# Sheet2.net
KiCad netlist of a schematic drawn in Altium Designer
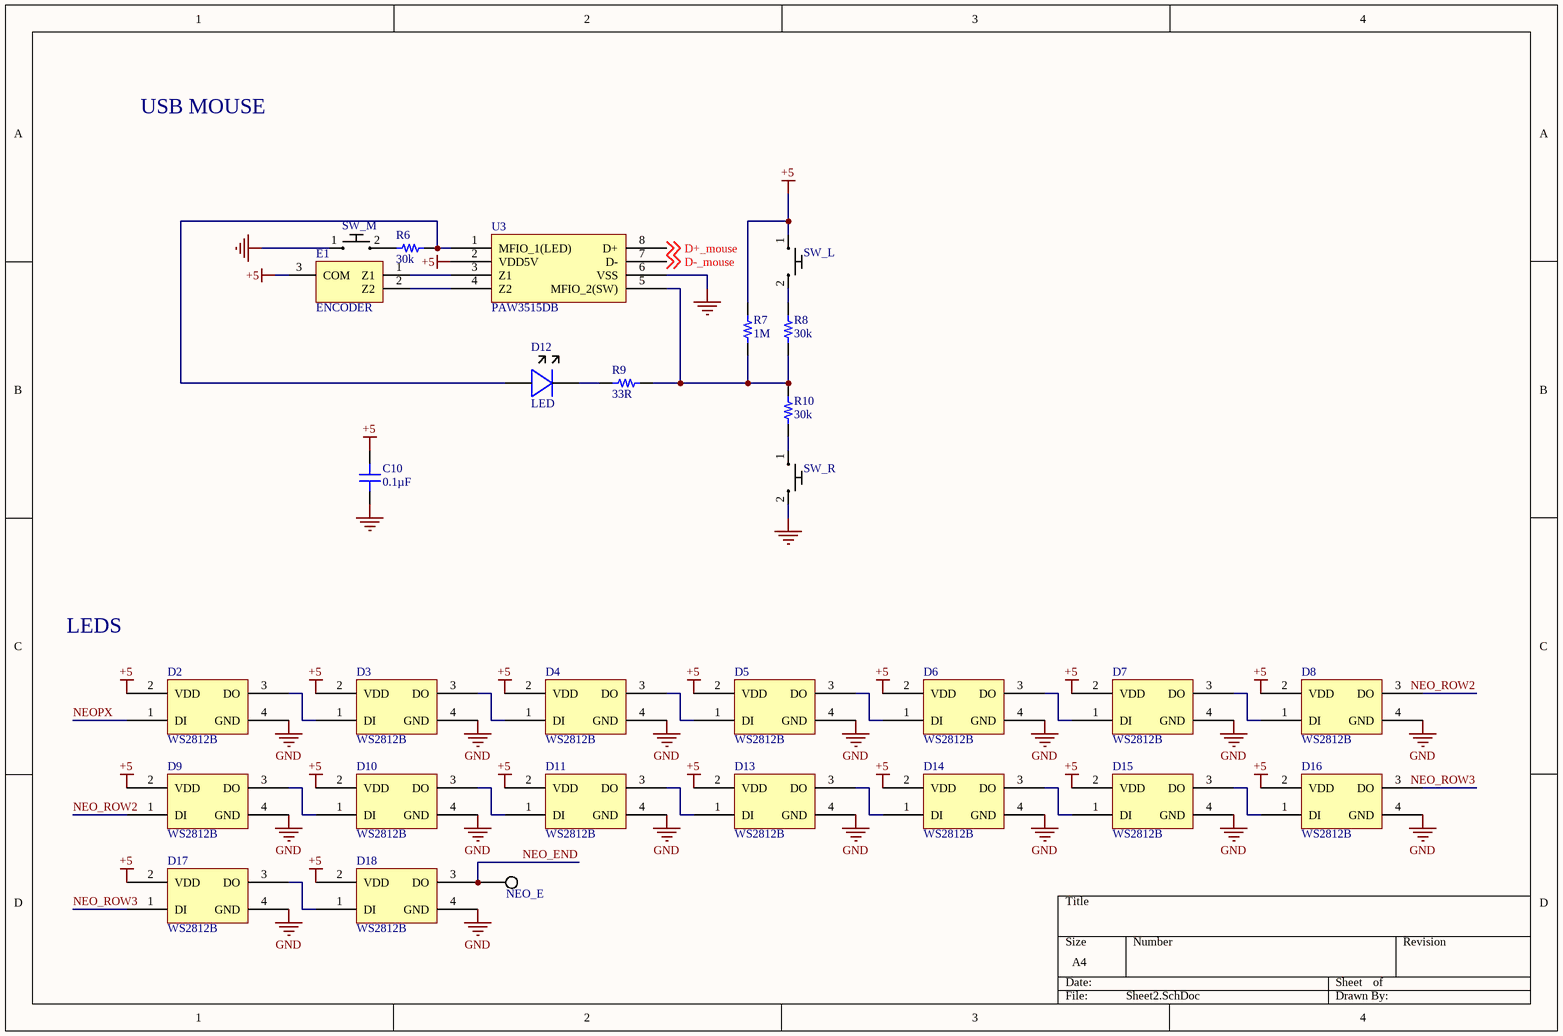
[diagram p0: Sheet2.SchDoc]

(export (version "E")
  (design (tool "Eeschema 10.0.6"))
  (components
    (comp (ref "C10")
      (value "0.1µF")
      (footprint "CAP 0603_1608")
      (description "CAP CER SMD 0603 .1UF 10% X7R 25")
      (fields
        (field (name "PART NUMBER") "CAP-RTZP49")
        (field (name "MANUFACTURER") "Samsung Electro-Mechanics")
      )
      (libsource (lib "Database_Libs_RenaudG") (part "Capacitor"))
    )
    (comp (ref "D2")
      (value "WS2812B")
      (footprint "WS2812B4020")
      (description "NEOPIXEL RGB LED")
      (fields (field (name "PART NUMBER") "DIO4020-RYIG4M") (field (name "MANUFACTURER") "Worldsemi"))
      (libsource (lib "Database_Libs_RenaudG") (part "NEOPIXEL-4020"))
    )
    (comp (ref "D3")
      (value "WS2812B")
      (footprint "WS2812B4020")
      (description "NEOPIXEL RGB LED")
      (fields (field (name "PART NUMBER") "DIO4020-RYIG4M") (field (name "MANUFACTURER") "Worldsemi"))
      (libsource (lib "Database_Libs_RenaudG") (part "NEOPIXEL-4020"))
    )
    (comp (ref "D4")
      (value "WS2812B")
      (footprint "WS2812B4020")
      (description "NEOPIXEL RGB LED")
      (fields (field (name "PART NUMBER") "DIO4020-RYIG4M") (field (name "MANUFACTURER") "Worldsemi"))
      (libsource (lib "Database_Libs_RenaudG") (part "NEOPIXEL-4020"))
    )
    (comp (ref "D5")
      (value "WS2812B")
      (footprint "WS2812B4020")
      (description "NEOPIXEL RGB LED")
      (fields (field (name "PART NUMBER") "DIO4020-RYIG4M") (field (name "MANUFACTURER") "Worldsemi"))
      (libsource (lib "Database_Libs_RenaudG") (part "NEOPIXEL-4020"))
    )
    (comp (ref "D6")
      (value "WS2812B")
      (footprint "WS2812B4020")
      (description "NEOPIXEL RGB LED")
      (fields (field (name "PART NUMBER") "DIO4020-RYIG4M") (field (name "MANUFACTURER") "Worldsemi"))
      (libsource (lib "Database_Libs_RenaudG") (part "NEOPIXEL-4020"))
    )
    (comp (ref "D7")
      (value "WS2812B")
      (footprint "WS2812B4020")
      (description "NEOPIXEL RGB LED")
      (fields (field (name "PART NUMBER") "DIO4020-RYIG4M") (field (name "MANUFACTURER") "Worldsemi"))
      (libsource (lib "Database_Libs_RenaudG") (part "NEOPIXEL-4020"))
    )
    (comp (ref "D8")
      (value "WS2812B")
      (footprint "WS2812B4020")
      (description "NEOPIXEL RGB LED")
      (fields (field (name "PART NUMBER") "DIO4020-RYIG4M") (field (name "MANUFACTURER") "Worldsemi"))
      (libsource (lib "Database_Libs_RenaudG") (part "NEOPIXEL-4020"))
    )
    (comp (ref "D9")
      (value "WS2812B")
      (footprint "WS2812B4020")
      (description "NEOPIXEL RGB LED")
      (fields (field (name "PART NUMBER") "DIO4020-RYIG4M") (field (name "MANUFACTURER") "Worldsemi"))
      (libsource (lib "Database_Libs_RenaudG") (part "NEOPIXEL-4020"))
    )
    (comp (ref "D10")
      (value "WS2812B")
      (footprint "WS2812B4020")
      (description "NEOPIXEL RGB LED")
      (fields (field (name "PART NUMBER") "DIO4020-RYIG4M") (field (name "MANUFACTURER") "Worldsemi"))
      (libsource (lib "Database_Libs_RenaudG") (part "NEOPIXEL-4020"))
    )
    (comp (ref "D11")
      (value "WS2812B")
      (footprint "WS2812B4020")
      (description "NEOPIXEL RGB LED")
      (fields (field (name "PART NUMBER") "DIO4020-RYIG4M") (field (name "MANUFACTURER") "Worldsemi"))
      (libsource (lib "Database_Libs_RenaudG") (part "NEOPIXEL-4020"))
    )
    (comp (ref "D12")
      (value "LED")
      (footprint "MOUSE_LED")
      (description "Optical mouse diode")
      (libsource (lib "Database_Libs_RenaudG") (part "LED"))
    )
    (comp (ref "D13")
      (value "WS2812B")
      (footprint "WS2812B4020")
      (description "NEOPIXEL RGB LED")
      (fields (field (name "PART NUMBER") "DIO4020-RYIG4M") (field (name "MANUFACTURER") "Worldsemi"))
      (libsource (lib "Database_Libs_RenaudG") (part "NEOPIXEL-4020"))
    )
    (comp (ref "D14")
      (value "WS2812B")
      (footprint "WS2812B4020")
      (description "NEOPIXEL RGB LED")
      (fields (field (name "PART NUMBER") "DIO4020-RYIG4M") (field (name "MANUFACTURER") "Worldsemi"))
      (libsource (lib "Database_Libs_RenaudG") (part "NEOPIXEL-4020"))
    )
    (comp (ref "D15")
      (value "WS2812B")
      (footprint "WS2812B4020")
      (description "NEOPIXEL RGB LED")
      (fields (field (name "PART NUMBER") "DIO4020-RYIG4M") (field (name "MANUFACTURER") "Worldsemi"))
      (libsource (lib "Database_Libs_RenaudG") (part "NEOPIXEL-4020"))
    )
    (comp (ref "D16")
      (value "WS2812B")
      (footprint "WS2812B4020")
      (description "NEOPIXEL RGB LED")
      (fields (field (name "PART NUMBER") "DIO4020-RYIG4M") (field (name "MANUFACTURER") "Worldsemi"))
      (libsource (lib "Database_Libs_RenaudG") (part "NEOPIXEL-4020"))
    )
    (comp (ref "D17")
      (value "WS2812B")
      (footprint "WS2812B4020")
      (description "NEOPIXEL RGB LED")
      (fields (field (name "PART NUMBER") "DIO4020-RYIG4M") (field (name "MANUFACTURER") "Worldsemi"))
      (libsource (lib "Database_Libs_RenaudG") (part "NEOPIXEL-4020"))
    )
    (comp (ref "D18")
      (value "WS2812B")
      (footprint "WS2812B4020")
      (description "NEOPIXEL RGB LED")
      (fields (field (name "PART NUMBER") "DIO4020-RYIG4M") (field (name "MANUFACTURER") "Worldsemi"))
      (libsource (lib "Database_Libs_RenaudG") (part "NEOPIXEL-4020"))
    )
    (comp (ref "E1")
      (value "ENCODER")
      (footprint "TTC_ENCODER")
      (description "Mouse wheel encoder")
      (fields (field (name "PART NUMBER") "MouseEncoder"))
      (libsource (lib "Database_Libs_RenaudG") (part "ENCODER"))
    )
    (comp (ref "NEO_E")
      (value "TestPoint")
      (footprint "TP2020")
      (description "PC TEST POINT MINIATURE")
      (fields (field (name "PART NUMBER") "JMP-RTZL7I") (field (name "MANUFACTURER") "Keystone Electronics"))
      (libsource (lib "Database_Libs_RenaudG") (part "TestPoint"))
    )
    (comp (ref "R6")
      (value "30k")
      (footprint "RES 0603_1608")
      (description "RES SMD 30K OHM 1% 1/10W 0603")
      (fields
        (field (name "PART NUMBER") "ERJ-3EKF3002V")
        (field (name "MANUFACTURER") "Panasonic Electronic Components")
      )
      (libsource (lib "Database_Libs_RenaudG") (part "Resistor"))
    )
    (comp (ref "R7")
      (value "1M")
      (footprint "RES 0603_1608")
      (description "RES SMD 1M OHM 1% 1/10W 0603")
      (fields
        (field (name "PART NUMBER") "ERJ-3EKF1004V")
        (field (name "MANUFACTURER") "Panasonic Electronic Components")
      )
      (libsource (lib "Database_Libs_RenaudG") (part "Resistor"))
    )
    (comp (ref "R8")
      (value "30k")
      (footprint "RES 0603_1608")
      (description "RES SMD 30K OHM 1% 1/10W 0603")
      (fields
        (field (name "PART NUMBER") "ERJ-3EKF3002V")
        (field (name "MANUFACTURER") "Panasonic Electronic Components")
      )
      (libsource (lib "Database_Libs_RenaudG") (part "Resistor"))
    )
    (comp (ref "R9")
      (value "33R")
      (footprint "RES 0603_1608")
      (description "RES SMD 33 OHM 1% 1/10W 0603")
      (fields
        (field (name "PART NUMBER") "ERJ-3EKF33R0V")
        (field (name "MANUFACTURER") "Panasonic Electronic Components")
      )
      (libsource (lib "Database_Libs_RenaudG") (part "Resistor"))
    )
    (comp (ref "R10")
      (value "30k")
      (footprint "RES 0603_1608")
      (description "RES SMD 30K OHM 1% 1/10W 0603")
      (fields
        (field (name "PART NUMBER") "ERJ-3EKF3002V")
        (field (name "MANUFACTURER") "Panasonic Electronic Components")
      )
      (libsource (lib "Database_Libs_RenaudG") (part "Resistor"))
    )
    (comp (ref "SW_L")
      (value "SPST_BUTTON")
      (footprint "KailhBtn")
      (description "Bouton of mouse click")
      (fields (field (name "PART NUMBER") "MouseClickBtn"))
      (libsource (lib "Database_Libs_RenaudG") (part "SPST_BUTTON"))
    )
    (comp (ref "SW_M")
      (value "SPST_BUTTON")
      (footprint "KailhBtn")
      (description "Bouton of mouse click")
      (fields (field (name "PART NUMBER") "MouseClickBtn"))
      (libsource (lib "Database_Libs_RenaudG") (part "SPST_BUTTON"))
    )
    (comp (ref "SW_R")
      (value "SPST_BUTTON")
      (footprint "KailhBtn")
      (description "Bouton of mouse click")
      (fields (field (name "PART NUMBER") "MouseClickBtn"))
      (libsource (lib "Database_Libs_RenaudG") (part "SPST_BUTTON"))
    )
    (comp (ref "U3")
      (value "PAW3515DB")
      (footprint "PAW3515DB")
      (description "Optical mouse sensor")
      (libsource (lib "Database_Libs_RenaudG") (part "PAW3515DB"))
    )
  )
  (nets
    (net (code "1") (name "+5") (class "Default")
      (node (ref "C10") (pin "2") (pinfunction "2_2") (pintype "passive"))
      (node (ref "D10") (pin "2") (pinfunction "VDD_2") (pintype "passive"))
      (node (ref "D11") (pin "2") (pinfunction "VDD_2") (pintype "passive"))
      (node (ref "D13") (pin "2") (pinfunction "VDD_2") (pintype "passive"))
      (node (ref "D14") (pin "2") (pinfunction "VDD_2") (pintype "passive"))
      (node (ref "D15") (pin "2") (pinfunction "VDD_2") (pintype "passive"))
      (node (ref "D16") (pin "2") (pinfunction "VDD_2") (pintype "passive"))
      (node (ref "D17") (pin "2") (pinfunction "VDD_2") (pintype "passive"))
      (node (ref "D18") (pin "2") (pinfunction "VDD_2") (pintype "passive"))
      (node (ref "D2") (pin "2") (pinfunction "VDD_2") (pintype "passive"))
      (node (ref "D3") (pin "2") (pinfunction "VDD_2") (pintype "passive"))
      (node (ref "D4") (pin "2") (pinfunction "VDD_2") (pintype "passive"))
      (node (ref "D5") (pin "2") (pinfunction "VDD_2") (pintype "passive"))
      (node (ref "D6") (pin "2") (pinfunction "VDD_2") (pintype "passive"))
      (node (ref "D7") (pin "2") (pinfunction "VDD_2") (pintype "passive"))
      (node (ref "D8") (pin "2") (pinfunction "VDD_2") (pintype "passive"))
      (node (ref "D9") (pin "2") (pinfunction "VDD_2") (pintype "passive"))
      (node (ref "E1") (pin "3") (pinfunction "COM_3") (pintype "passive"))
      (node (ref "R7") (pin "2") (pinfunction "2_2") (pintype "passive"))
      (node (ref "SW_L") (pin "1") (pinfunction "1_1") (pintype "passive"))
      (node (ref "U3") (pin "2") (pinfunction "VDD5V_2") (pintype "passive"))
    )
    (net (code "2") (name "/NEOPX") (class "Default")
      (node (ref "D2") (pin "1") (pinfunction "DI_1") (pintype "passive"))
    )
    (net (code "3") (name "/NEO_END") (class "Default")
      (node (ref "D18") (pin "3") (pinfunction "DO_3") (pintype "passive"))
      (node (ref "NEO_E") (pin "TP") (pintype "passive"))
    )
    (net (code "4") (name "/NEO_ROW2") (class "Default")
      (node (ref "D8") (pin "3") (pinfunction "DO_3") (pintype "passive"))
      (node (ref "D9") (pin "1") (pinfunction "DI_1") (pintype "passive"))
    )
    (net (code "5") (name "/NEO_ROW3") (class "Default")
      (node (ref "D16") (pin "3") (pinfunction "DO_3") (pintype "passive"))
      (node (ref "D17") (pin "1") (pinfunction "DI_1") (pintype "passive"))
    )
    (net (code "6") (name "D+_mouse") (class "Default")
      (node (ref "U3") (pin "8") (pinfunction "D+_8") (pintype "passive"))
    )
    (net (code "7") (name "D-_mouse") (class "Default")
      (node (ref "U3") (pin "7") (pinfunction "D-_7") (pintype "passive"))
    )
    (net (code "8") (name "GND") (class "Default")
      (node (ref "C10") (pin "1") (pinfunction "1_1") (pintype "passive"))
      (node (ref "D10") (pin "4") (pinfunction "GND_4") (pintype "passive"))
      (node (ref "D11") (pin "4") (pinfunction "GND_4") (pintype "passive"))
      (node (ref "D13") (pin "4") (pinfunction "GND_4") (pintype "passive"))
      (node (ref "D14") (pin "4") (pinfunction "GND_4") (pintype "passive"))
      (node (ref "D15") (pin "4") (pinfunction "GND_4") (pintype "passive"))
      (node (ref "D16") (pin "4") (pinfunction "GND_4") (pintype "passive"))
      (node (ref "D17") (pin "4") (pinfunction "GND_4") (pintype "passive"))
      (node (ref "D18") (pin "4") (pinfunction "GND_4") (pintype "passive"))
      (node (ref "D2") (pin "4") (pinfunction "GND_4") (pintype "passive"))
      (node (ref "D3") (pin "4") (pinfunction "GND_4") (pintype "passive"))
      (node (ref "D4") (pin "4") (pinfunction "GND_4") (pintype "passive"))
      (node (ref "D5") (pin "4") (pinfunction "GND_4") (pintype "passive"))
      (node (ref "D6") (pin "4") (pinfunction "GND_4") (pintype "passive"))
      (node (ref "D7") (pin "4") (pinfunction "GND_4") (pintype "passive"))
      (node (ref "D8") (pin "4") (pinfunction "GND_4") (pintype "passive"))
      (node (ref "D9") (pin "4") (pinfunction "GND_4") (pintype "passive"))
      (node (ref "SW_M") (pin "1") (pinfunction "1_1") (pintype "passive"))
      (node (ref "SW_R") (pin "2") (pinfunction "2_2") (pintype "passive"))
      (node (ref "U3") (pin "6") (pinfunction "VSS_6") (pintype "passive"))
    )
    (net (code "9") (name "Net-(D2-DO)") (class "Default")
      (node (ref "D2") (pin "3") (pinfunction "DO_3") (pintype "passive"))
      (node (ref "D3") (pin "1") (pinfunction "DI_1") (pintype "passive"))
    )
    (net (code "10") (name "Net-(D3-DO)") (class "Default")
      (node (ref "D3") (pin "3") (pinfunction "DO_3") (pintype "passive"))
      (node (ref "D4") (pin "1") (pinfunction "DI_1") (pintype "passive"))
    )
    (net (code "11") (name "Net-(D4-DO)") (class "Default")
      (node (ref "D4") (pin "3") (pinfunction "DO_3") (pintype "passive"))
      (node (ref "D5") (pin "1") (pinfunction "DI_1") (pintype "passive"))
    )
    (net (code "12") (name "Net-(D5-DO)") (class "Default")
      (node (ref "D5") (pin "3") (pinfunction "DO_3") (pintype "passive"))
      (node (ref "D6") (pin "1") (pinfunction "DI_1") (pintype "passive"))
    )
    (net (code "13") (name "Net-(D6-DO)") (class "Default")
      (node (ref "D6") (pin "3") (pinfunction "DO_3") (pintype "passive"))
      (node (ref "D7") (pin "1") (pinfunction "DI_1") (pintype "passive"))
    )
    (net (code "14") (name "Net-(D7-DO)") (class "Default")
      (node (ref "D7") (pin "3") (pinfunction "DO_3") (pintype "passive"))
      (node (ref "D8") (pin "1") (pinfunction "DI_1") (pintype "passive"))
    )
    (net (code "15") (name "Net-(D10-DI)") (class "Default")
      (node (ref "D10") (pin "1") (pinfunction "DI_1") (pintype "passive"))
      (node (ref "D9") (pin "3") (pinfunction "DO_3") (pintype "passive"))
    )
    (net (code "16") (name "Net-(D10-DO)") (class "Default")
      (node (ref "D10") (pin "3") (pinfunction "DO_3") (pintype "passive"))
      (node (ref "D11") (pin "1") (pinfunction "DI_1") (pintype "passive"))
    )
    (net (code "17") (name "Net-(D11-DO)") (class "Default")
      (node (ref "D11") (pin "3") (pinfunction "DO_3") (pintype "passive"))
      (node (ref "D13") (pin "1") (pinfunction "DI_1") (pintype "passive"))
    )
    (net (code "18") (name "Net-(D12-PadK)") (class "Default")
      (node (ref "D12") (pin "K") (pinfunction "K_K") (pintype "passive"))
      (node (ref "R9") (pin "1") (pinfunction "1_1") (pintype "passive"))
    )
    (net (code "19") (name "Net-(D13-DO)") (class "Default")
      (node (ref "D13") (pin "3") (pinfunction "DO_3") (pintype "passive"))
      (node (ref "D14") (pin "1") (pinfunction "DI_1") (pintype "passive"))
    )
    (net (code "20") (name "Net-(D14-DO)") (class "Default")
      (node (ref "D14") (pin "3") (pinfunction "DO_3") (pintype "passive"))
      (node (ref "D15") (pin "1") (pinfunction "DI_1") (pintype "passive"))
    )
    (net (code "21") (name "Net-(D15-DO)") (class "Default")
      (node (ref "D15") (pin "3") (pinfunction "DO_3") (pintype "passive"))
      (node (ref "D16") (pin "1") (pinfunction "DI_1") (pintype "passive"))
    )
    (net (code "22") (name "Net-(D17-DO)") (class "Default")
      (node (ref "D17") (pin "3") (pinfunction "DO_3") (pintype "passive"))
      (node (ref "D18") (pin "1") (pinfunction "DI_1") (pintype "passive"))
    )
    (net (code "23") (name "Net-(E1-Z1)") (class "Default")
      (node (ref "E1") (pin "1") (pinfunction "Z1_1") (pintype "passive"))
      (node (ref "U3") (pin "3") (pinfunction "Z1_3") (pintype "passive"))
    )
    (net (code "24") (name "Net-(E1-Z2)") (class "Default")
      (node (ref "E1") (pin "2") (pinfunction "Z2_2") (pintype "passive"))
      (node (ref "U3") (pin "4") (pinfunction "Z2_4") (pintype "passive"))
    )
    (net (code "25") (name "Net-(R6-Pad1)") (class "Default")
      (node (ref "R6") (pin "1") (pinfunction "1_1") (pintype "passive"))
      (node (ref "SW_M") (pin "2") (pinfunction "2_2") (pintype "passive"))
    )
    (net (code "26") (name "Net-(R8-Pad2)") (class "Default")
      (node (ref "R8") (pin "2") (pinfunction "2_2") (pintype "passive"))
      (node (ref "SW_L") (pin "2") (pinfunction "2_2") (pintype "passive"))
    )
    (net (code "27") (name "Net-(R10-Pad1)") (class "Default")
      (node (ref "R10") (pin "1") (pinfunction "1_1") (pintype "passive"))
      (node (ref "SW_R") (pin "1") (pinfunction "1_1") (pintype "passive"))
    )
    (net (code "28") (name "Net-(U3-MFIO_1(LED))") (class "Default")
      (node (ref "D12") (pin "A") (pinfunction "A_A") (pintype "passive"))
      (node (ref "R6") (pin "2") (pinfunction "2_2") (pintype "passive"))
      (node (ref "U3") (pin "1") (pinfunction "MFIO_1(LED)_1") (pintype "passive"))
    )
    (net (code "29") (name "Net-(U3-MFIO_2(SW))") (class "Default")
      (node (ref "R10") (pin "2") (pinfunction "2_2") (pintype "passive"))
      (node (ref "R7") (pin "1") (pinfunction "1_1") (pintype "passive"))
      (node (ref "R8") (pin "1") (pinfunction "1_1") (pintype "passive"))
      (node (ref "R9") (pin "2") (pinfunction "2_2") (pintype "passive"))
      (node (ref "U3") (pin "5") (pinfunction "MFIO_2(SW)_5") (pintype "passive"))
    )
  )
)
